# KMO_IO_MV1_2.net
KiCad netlist of a schematic drawn in EAGLE
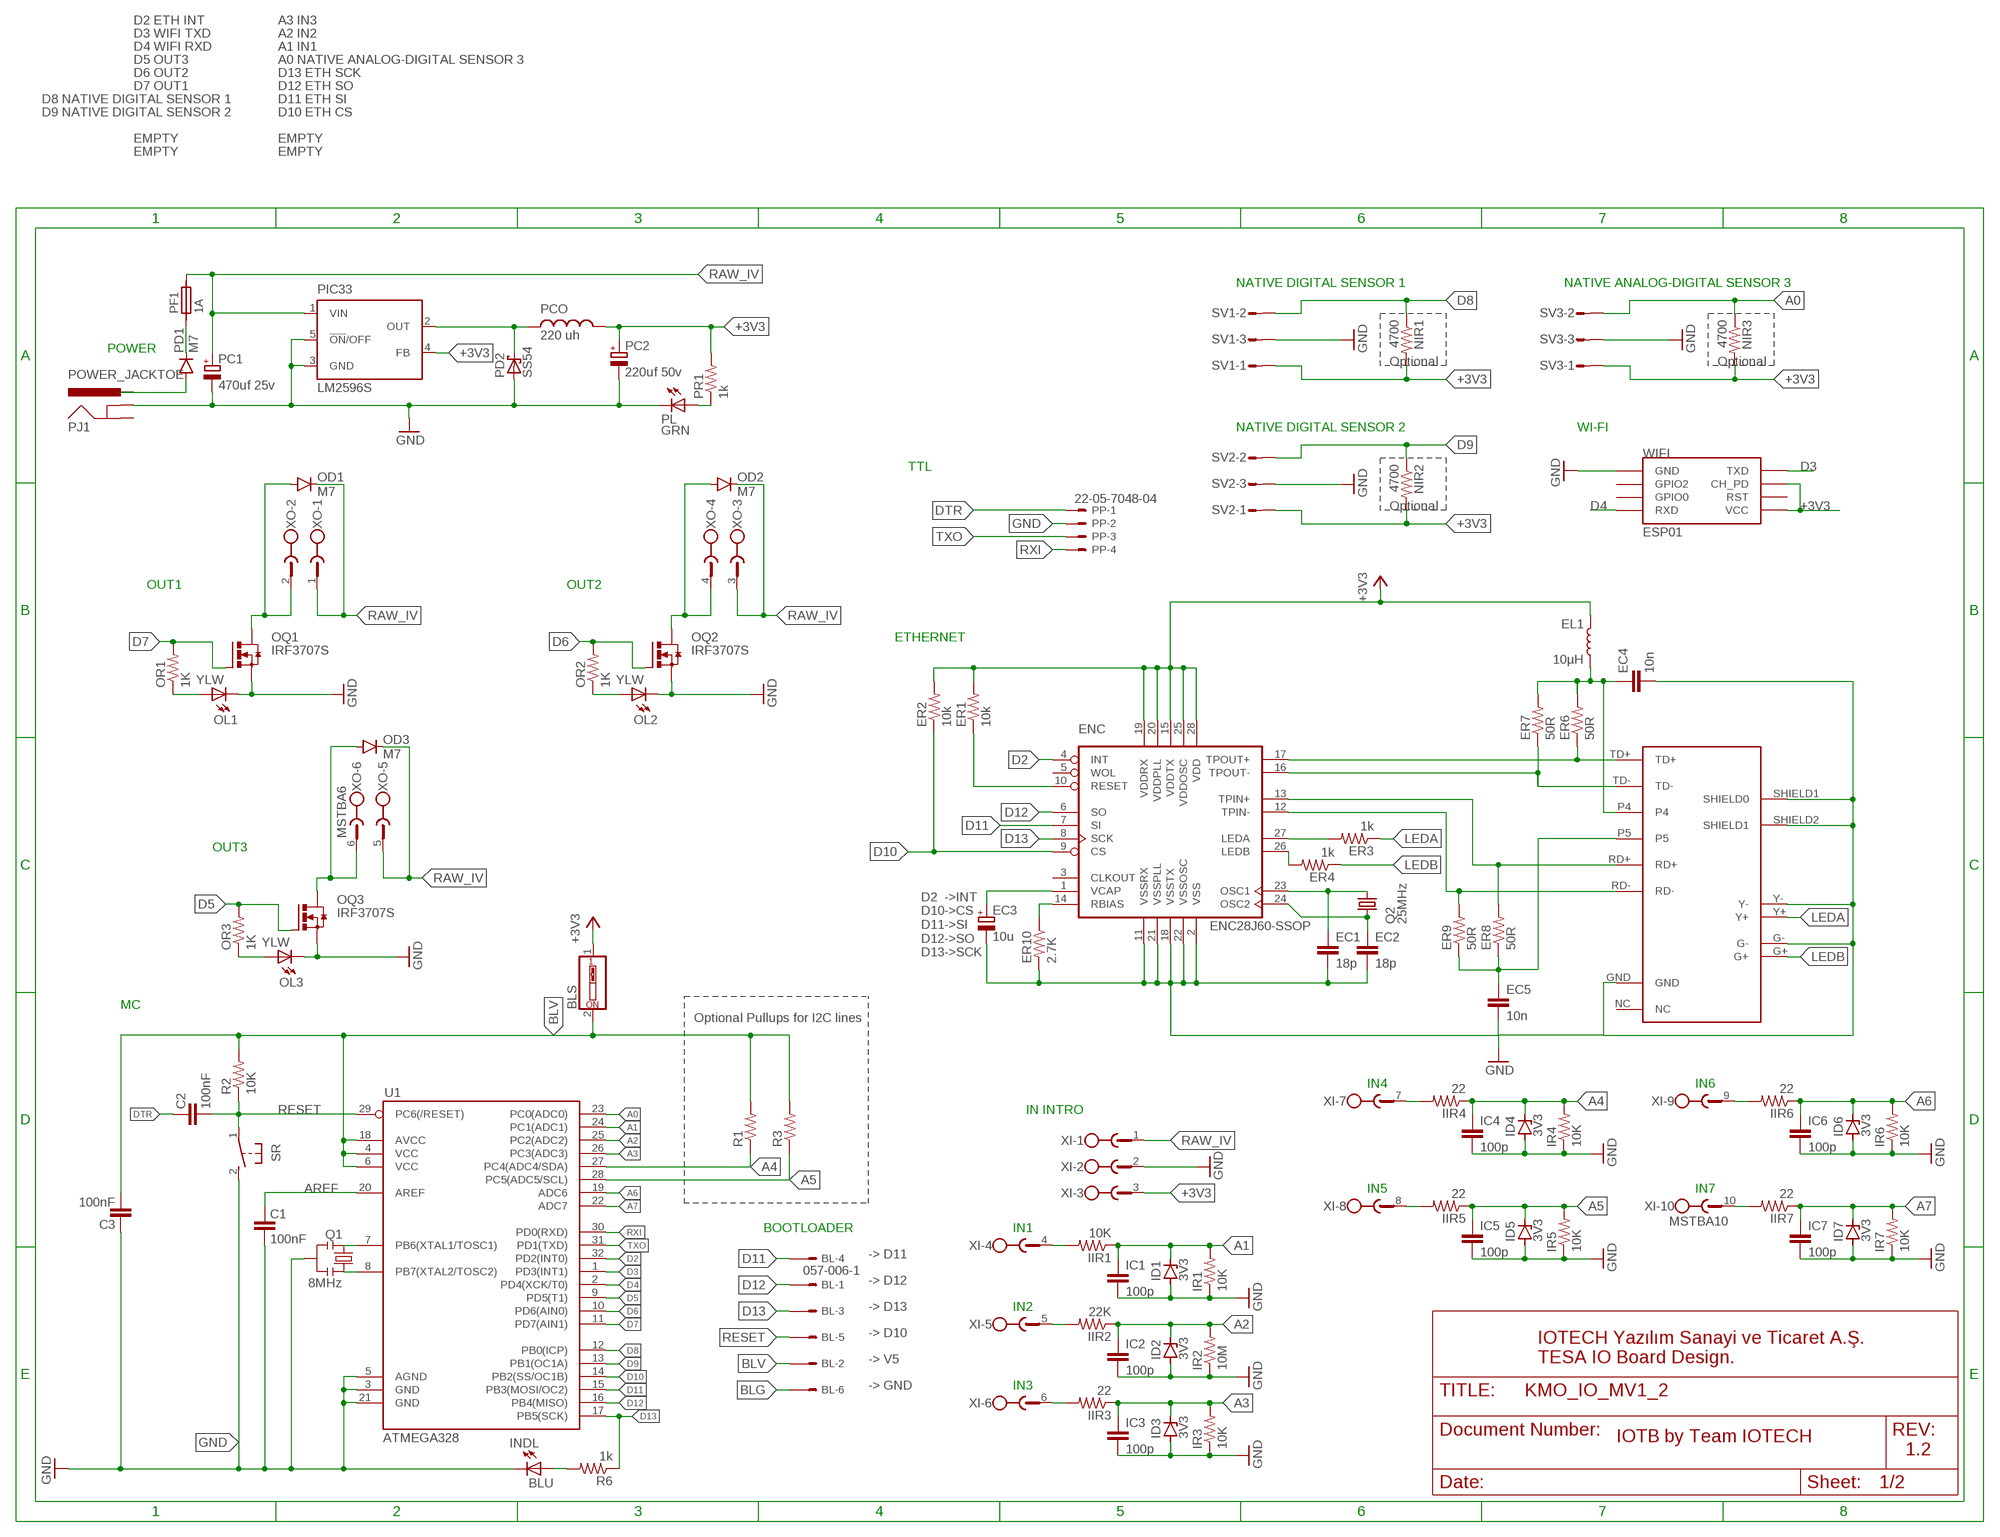
[diagram p0: schematic, sheet 1]
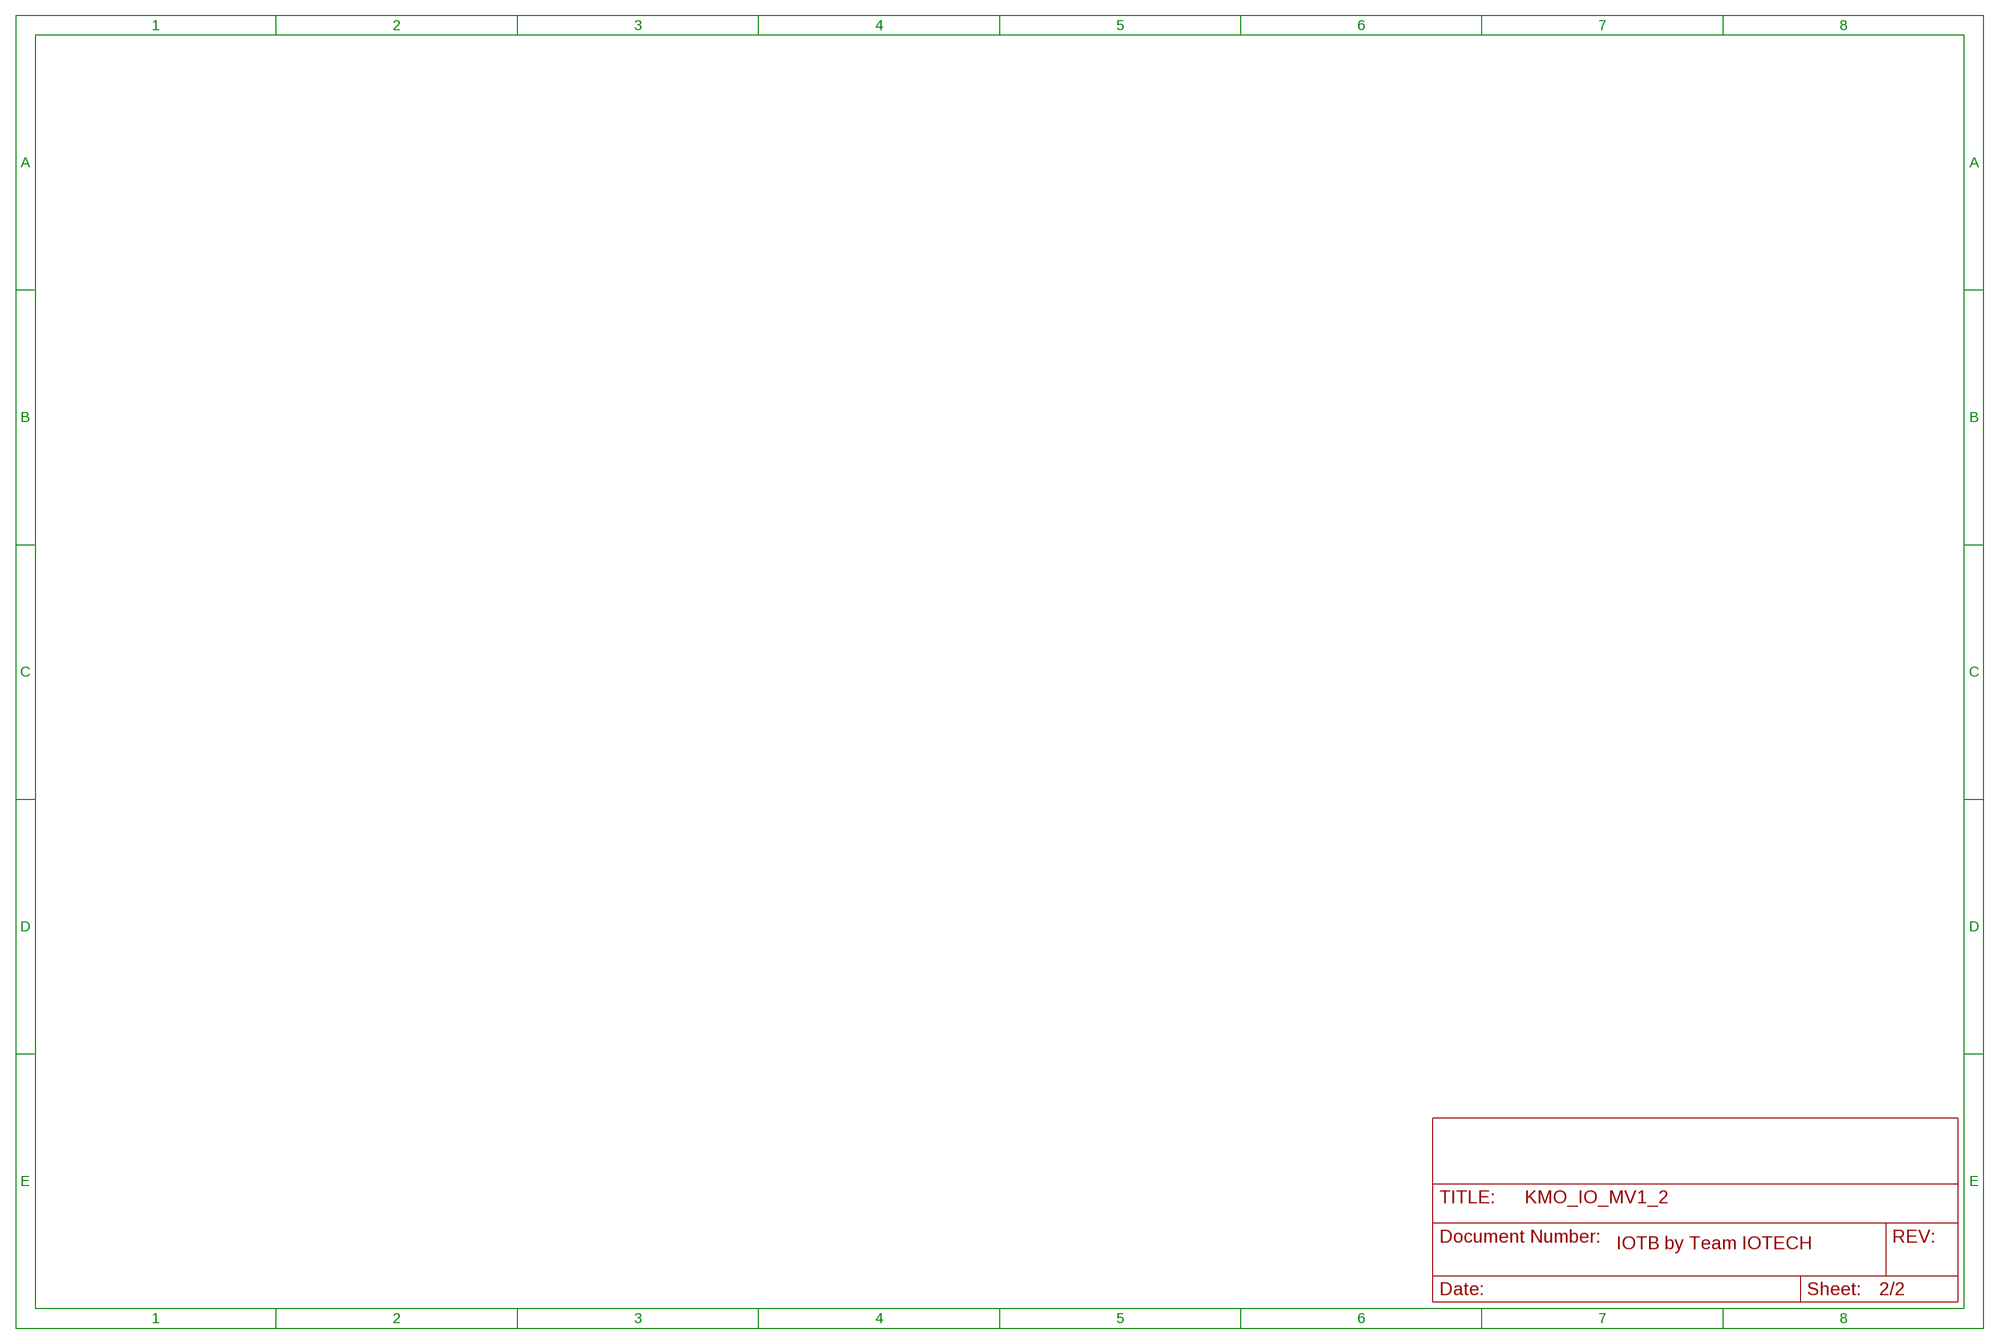
[diagram p1: schematic, sheet 2]

(export (version "E")
  (design (tool "Eeschema 10.0.6"))
  (components
    (comp (ref "BL")
      (value "057-006-1")
      (footprint "eagle-import:057-006-1")
      (libsource (lib "eagle-import") (part "057-006-1"))
    )
    (comp (ref "BLS")
      (value "SW_DIP-1")
      (footprint "eagle-import:EDG-01")
      (libsource (lib "eagle-import") (part "SW_DIP-1"))
    )
    (comp (ref "C1")
      (value "100nF")
      (footprint "eagle-import:0805")
      (libsource (lib "eagle-import") (part "CAP0805"))
    )
    (comp (ref "C2")
      (value "100nF")
      (footprint "eagle-import:0805")
      (libsource (lib "eagle-import") (part "CAP0805"))
    )
    (comp (ref "C3")
      (value "100nF")
      (footprint "eagle-import:0805")
      (libsource (lib "eagle-import") (part "CAP0805"))
    )
    (comp (ref "EC1")
      (value "18p")
      (footprint "eagle-import:0805")
      (libsource (lib "eagle-import") (part "CAP0805"))
    )
    (comp (ref "EC2")
      (value "18p")
      (footprint "eagle-import:0805")
      (libsource (lib "eagle-import") (part "CAP0805"))
    )
    (comp (ref "EC3")
      (value "10u")
      (footprint "eagle-import:CT3216")
      (libsource (lib "eagle-import") (part "CPOL-EUCT3216"))
    )
    (comp (ref "EC4")
      (value "10n")
      (footprint "eagle-import:0805")
      (libsource (lib "eagle-import") (part "CAP0805"))
    )
    (comp (ref "EC5")
      (value "10n")
      (footprint "eagle-import:0805")
      (libsource (lib "eagle-import") (part "CAP0805"))
    )
    (comp (ref "EL1")
      (value "10µH")
      (footprint "eagle-import:0805")
      (libsource (lib "eagle-import") (part "INDUCTOR-0805-3.3UH"))
    )
    (comp (ref "ENC")
      (value "ENC28J60-SSOP")
      (footprint "eagle-import:SSOP28")
      (libsource (lib "eagle-import") (part "ENC28J60-SSOP"))
    )
    (comp (ref "ER1")
      (value "10k")
      (footprint "eagle-import:0805")
      (libsource (lib "eagle-import") (part "RESISTOR0805-RES"))
    )
    (comp (ref "ER2")
      (value "10k")
      (footprint "eagle-import:0805")
      (libsource (lib "eagle-import") (part "RESISTOR0805-RES"))
    )
    (comp (ref "ER3")
      (value "1k")
      (footprint "eagle-import:0805")
      (libsource (lib "eagle-import") (part "RESISTOR0805-RES"))
    )
    (comp (ref "ER4")
      (value "1k")
      (footprint "eagle-import:0805")
      (libsource (lib "eagle-import") (part "RESISTOR0805-RES"))
    )
    (comp (ref "ER6")
      (value "50R")
      (footprint "eagle-import:0805")
      (libsource (lib "eagle-import") (part "RESISTOR0805-RES"))
    )
    (comp (ref "ER7")
      (value "50R")
      (footprint "eagle-import:0805")
      (libsource (lib "eagle-import") (part "RESISTOR0805-RES"))
    )
    (comp (ref "ER8")
      (value "50R")
      (footprint "eagle-import:0805")
      (libsource (lib "eagle-import") (part "RESISTOR0805-RES"))
    )
    (comp (ref "ER9")
      (value "50R")
      (footprint "eagle-import:0805")
      (libsource (lib "eagle-import") (part "RESISTOR0805-RES"))
    )
    (comp (ref "ER10")
      (value "2.7K")
      (footprint "eagle-import:0805")
      (libsource (lib "eagle-import") (part "RESISTOR0805-RES"))
    )
    (comp (ref "IC1")
      (value "100p")
      (footprint "eagle-import:0805")
      (libsource (lib "eagle-import") (part "CAP0805"))
    )
    (comp (ref "IC2")
      (value "100p")
      (footprint "eagle-import:0805")
      (libsource (lib "eagle-import") (part "CAP0805"))
    )
    (comp (ref "IC3")
      (value "100p")
      (footprint "eagle-import:0805")
      (libsource (lib "eagle-import") (part "CAP0805"))
    )
    (comp (ref "IC4")
      (value "100p")
      (footprint "eagle-import:0805")
      (libsource (lib "eagle-import") (part "CAP0805"))
    )
    (comp (ref "IC5")
      (value "100p")
      (footprint "eagle-import:0805")
      (libsource (lib "eagle-import") (part "CAP0805"))
    )
    (comp (ref "IC6")
      (value "100p")
      (footprint "eagle-import:0805")
      (libsource (lib "eagle-import") (part "CAP0805"))
    )
    (comp (ref "IC7")
      (value "100p")
      (footprint "eagle-import:0805")
      (libsource (lib "eagle-import") (part "CAP0805"))
    )
    (comp (ref "ID1")
      (value "3V3")
      (footprint "eagle-import:SOT23")
      (libsource (lib "eagle-import") (part "ZENER-DIODESOT23"))
    )
    (comp (ref "ID2")
      (value "3V3")
      (footprint "eagle-import:SOT23")
      (libsource (lib "eagle-import") (part "ZENER-DIODESOT23"))
    )
    (comp (ref "ID3")
      (value "3V3")
      (footprint "eagle-import:SOT23")
      (libsource (lib "eagle-import") (part "ZENER-DIODESOT23"))
    )
    (comp (ref "ID4")
      (value "3V3")
      (footprint "eagle-import:SOT23")
      (libsource (lib "eagle-import") (part "ZENER-DIODESOT23"))
    )
    (comp (ref "ID5")
      (value "3V3")
      (footprint "eagle-import:SOT23")
      (libsource (lib "eagle-import") (part "ZENER-DIODESOT23"))
    )
    (comp (ref "ID6")
      (value "3V3")
      (footprint "eagle-import:SOT23")
      (libsource (lib "eagle-import") (part "ZENER-DIODESOT23"))
    )
    (comp (ref "ID7")
      (value "3V3")
      (footprint "eagle-import:SOT23")
      (libsource (lib "eagle-import") (part "ZENER-DIODESOT23"))
    )
    (comp (ref "IIR1")
      (value "10K")
      (footprint "eagle-import:0805")
      (libsource (lib "eagle-import") (part "RESISTOR0805-RES"))
    )
    (comp (ref "IIR2")
      (value "22K")
      (footprint "eagle-import:0805")
      (libsource (lib "eagle-import") (part "RESISTOR0805-RES"))
    )
    (comp (ref "IIR3")
      (value "22")
      (footprint "eagle-import:0805")
      (libsource (lib "eagle-import") (part "RESISTOR0805-RES"))
    )
    (comp (ref "IIR4")
      (value "22")
      (footprint "eagle-import:0805")
      (libsource (lib "eagle-import") (part "RESISTOR0805-RES"))
    )
    (comp (ref "IIR5")
      (value "22")
      (footprint "eagle-import:0805")
      (libsource (lib "eagle-import") (part "RESISTOR0805-RES"))
    )
    (comp (ref "IIR6")
      (value "22")
      (footprint "eagle-import:0805")
      (libsource (lib "eagle-import") (part "RESISTOR0805-RES"))
    )
    (comp (ref "IIR7")
      (value "22")
      (footprint "eagle-import:0805")
      (libsource (lib "eagle-import") (part "RESISTOR0805-RES"))
    )
    (comp (ref "INDL")
      (value "BLU")
      (footprint "eagle-import:CHIP-LED0805")
      (libsource (lib "eagle-import") (part "LEDCHIP-LED0805"))
    )
    (comp (ref "IR1")
      (value "10K")
      (footprint "eagle-import:0805")
      (libsource (lib "eagle-import") (part "RESISTOR0805-RES"))
    )
    (comp (ref "IR2")
      (value "10M")
      (footprint "eagle-import:0805")
      (libsource (lib "eagle-import") (part "RESISTOR0805-RES"))
    )
    (comp (ref "IR3")
      (value "10K")
      (footprint "eagle-import:0805")
      (libsource (lib "eagle-import") (part "RESISTOR0805-RES"))
    )
    (comp (ref "IR4")
      (value "10K")
      (footprint "eagle-import:0805")
      (libsource (lib "eagle-import") (part "RESISTOR0805-RES"))
    )
    (comp (ref "IR5")
      (value "10K")
      (footprint "eagle-import:0805")
      (libsource (lib "eagle-import") (part "RESISTOR0805-RES"))
    )
    (comp (ref "IR6")
      (value "10K")
      (footprint "eagle-import:0805")
      (libsource (lib "eagle-import") (part "RESISTOR0805-RES"))
    )
    (comp (ref "IR7")
      (value "10K")
      (footprint "eagle-import:0805")
      (libsource (lib "eagle-import") (part "RESISTOR0805-RES"))
    )
    (comp (ref "NIR1")
      (value "4700")
      (footprint "eagle-import:0805")
      (libsource (lib "eagle-import") (part "RESISTOR0805-RES"))
    )
    (comp (ref "NIR2")
      (value "4700")
      (footprint "eagle-import:0805")
      (libsource (lib "eagle-import") (part "RESISTOR0805-RES"))
    )
    (comp (ref "NIR3")
      (value "4700")
      (footprint "eagle-import:0805")
      (libsource (lib "eagle-import") (part "RESISTOR0805-RES"))
    )
    (comp (ref "OD1")
      (value "M7")
      (footprint "eagle-import:SMA-DIODE")
      (libsource (lib "eagle-import") (part "DIODESMA"))
    )
    (comp (ref "OD2")
      (value "M7")
      (footprint "eagle-import:SMA-DIODE")
      (libsource (lib "eagle-import") (part "DIODESMA"))
    )
    (comp (ref "OD3")
      (value "M7")
      (footprint "eagle-import:SMA-DIODE")
      (libsource (lib "eagle-import") (part "DIODESMA"))
    )
    (comp (ref "OL1")
      (value "YLW")
      (footprint "eagle-import:CHIP-LED0805")
      (libsource (lib "eagle-import") (part "LEDCHIP-LED0805"))
    )
    (comp (ref "OL2")
      (value "YLW")
      (footprint "eagle-import:CHIP-LED0805")
      (libsource (lib "eagle-import") (part "LEDCHIP-LED0805"))
    )
    (comp (ref "OL3")
      (value "YLW")
      (footprint "eagle-import:CHIP-LED0805")
      (libsource (lib "eagle-import") (part "LEDCHIP-LED0805"))
    )
    (comp (ref "OQ1")
      (value "IRF3707S")
      (footprint "eagle-import:D2PACK")
      (libsource (lib "eagle-import") (part "IRF3704S"))
    )
    (comp (ref "OQ2")
      (value "IRF3707S")
      (footprint "eagle-import:D2PACK")
      (libsource (lib "eagle-import") (part "IRF3704S"))
    )
    (comp (ref "OQ3")
      (value "IRF3707S")
      (footprint "eagle-import:D2PACK")
      (libsource (lib "eagle-import") (part "IRF3704S"))
    )
    (comp (ref "OR1")
      (value "1K")
      (footprint "eagle-import:0805")
      (libsource (lib "eagle-import") (part "RESISTOR0805-RES"))
    )
    (comp (ref "OR2")
      (value "1K")
      (footprint "eagle-import:0805")
      (libsource (lib "eagle-import") (part "RESISTOR0805-RES"))
    )
    (comp (ref "OR3")
      (value "1K")
      (footprint "eagle-import:0805")
      (libsource (lib "eagle-import") (part "RESISTOR0805-RES"))
    )
    (comp (ref "PC1")
      (value "470uf 25v")
      (footprint "eagle-import:140CLH-1010")
      (libsource (lib "eagle-import") (part "CPOL-EU140CLH-1010"))
    )
    (comp (ref "PC2")
      (value "220uf 50v")
      (footprint "eagle-import:140CLH-1010")
      (libsource (lib "eagle-import") (part "CPOL-EU140CLH-1010"))
    )
    (comp (ref "PCO")
      (value "220 uh")
      (footprint "eagle-import:MSS1260")
      (libsource (lib "eagle-import") (part "MSS1260"))
    )
    (comp (ref "PD1")
      (value "M7")
      (footprint "eagle-import:SMA-DIODE")
      (libsource (lib "eagle-import") (part "DIODESMA"))
    )
    (comp (ref "PD2")
      (value "SS54")
      (footprint "eagle-import:SMB")
      (libsource (lib "eagle-import") (part "SCHOTTKY-DIODESMD"))
    )
    (comp (ref "PF1")
      (value "1A")
      (footprint "eagle-import:1820")
      (libsource (lib "eagle-import") (part "SIBA194600"))
    )
    (comp (ref "PIC33")
      (value "LM2596S")
      (footprint "eagle-import:TO263-5")
      (fields (field (name "MF") "NATIONAL SEMICONDUCTOR") (field (name "MPN") "LM2596S-ADJ/NOPB"))
      (libsource (lib "eagle-import") (part "LM2596S"))
    )
    (comp (ref "PJ1")
      (value "POWER_JACKTOE")
      (footprint "eagle-import:POWER_JACK_SMD_OVERPASTE_TOE")
      (libsource (lib "eagle-import") (part "POWER_JACKTOE"))
    )
    (comp (ref "PL")
      (value "GRN")
      (footprint "eagle-import:CHIP-LED0805")
      (libsource (lib "eagle-import") (part "LEDCHIP-LED0805"))
    )
    (comp (ref "PP")
      (value "22-05-7048-04")
      (footprint "eagle-import:7395-04")
      (fields (field (name "MF") "MOLEX"))
      (libsource (lib "eagle-import") (part "22-?-0405-7048"))
    )
    (comp (ref "PR1")
      (value "1k")
      (footprint "eagle-import:0805")
      (libsource (lib "eagle-import") (part "RESISTOR0805-RES"))
    )
    (comp (ref "Q1")
      (value "8MHz")
      (footprint "eagle-import:RESONATOR-SMD-1_1")
      (libsource (lib "eagle-import") (part "RESONATOR1{colon}1"))
    )
    (comp (ref "Q2")
      (value "25MHz")
      (footprint "eagle-import:5.0X3.2_2")
      (libsource (lib "eagle-import") (part "KX-9B"))
    )
    (comp (ref "R1")
      (value "RESISTOR0805-RES")
      (footprint "eagle-import:0805")
      (libsource (lib "eagle-import") (part "RESISTOR0805-RES"))
    )
    (comp (ref "R2")
      (value "10K")
      (footprint "eagle-import:0805")
      (libsource (lib "eagle-import") (part "RESISTOR0805-RES"))
    )
    (comp (ref "R3")
      (value "RESISTOR0805-RES")
      (footprint "eagle-import:0805")
      (libsource (lib "eagle-import") (part "RESISTOR0805-RES"))
    )
    (comp (ref "R6")
      (value "1k")
      (footprint "eagle-import:0805")
      (libsource (lib "eagle-import") (part "RESISTOR0805-RES"))
    )
    (comp (ref "SR")
      (value "31-XX")
      (footprint "eagle-import:B3F-31XX")
      (fields (field (name "MPN") "B3F-3100"))
      (libsource (lib "eagle-import") (part "31-XX"))
    )
    (comp (ref "SV1")
      (value "S03P")
      (footprint "eagle-import:S03P")
      (libsource (lib "eagle-import") (part "S03P"))
    )
    (comp (ref "SV2")
      (value "S03P")
      (footprint "eagle-import:S03P")
      (libsource (lib "eagle-import") (part "S03P"))
    )
    (comp (ref "SV3")
      (value "S03P")
      (footprint "eagle-import:S03P")
      (libsource (lib "eagle-import") (part "S03P"))
    )
    (comp (ref "U$2")
      (value "HR911105A")
      (footprint "eagle-import:RJ45")
      (libsource (lib "eagle-import") (part "HR911105A"))
    )
    (comp (ref "U1")
      (value "ATMEGA328")
      (footprint "eagle-import:TQFP32-08")
      (libsource (lib "eagle-import") (part "ATMEGA168"))
    )
    (comp (ref "WIFI")
      (value "ESP01")
      (footprint "eagle-import:ESP01")
      (libsource (lib "eagle-import") (part "ESP01"))
    )
    (comp (ref "XI")
      (value "MSTBA10")
      (footprint "eagle-import:MSTBA10")
      (fields (field (name "MF") "FARNELL") (field (name "MPN") "1757323"))
      (libsource (lib "eagle-import") (part "MSTBA10"))
    )
    (comp (ref "XO")
      (value "MSTBA6")
      (footprint "eagle-import:MSTBA6")
      (fields (field (name "MF") "FARNELL") (field (name "MPN") "1757284"))
      (libsource (lib "eagle-import") (part "MSTBA6"))
    )
  )
  (nets
    (net (code "1") (name "+3V3") (class "Default")
      (node (ref "BLS") (pin "1") (pinfunction "1_1") (pintype "passive"))
      (node (ref "EL1") (pin "1") (pinfunction "1_1") (pintype "passive"))
      (node (ref "ENC") (pin "15") (pinfunction "VDDTX_15") (pintype "power_in"))
      (node (ref "ENC") (pin "19") (pinfunction "VDDRX_19") (pintype "power_in"))
      (node (ref "ENC") (pin "20") (pinfunction "VDDPLL_20") (pintype "power_in"))
      (node (ref "ENC") (pin "25") (pinfunction "VDDOSC_25") (pintype "power_in"))
      (node (ref "ENC") (pin "28") (pinfunction "VDD_28") (pintype "power_in"))
      (node (ref "ER1") (pin "2") (pinfunction "2_2") (pintype "passive"))
      (node (ref "ER2") (pin "2") (pinfunction "2_2") (pintype "passive"))
      (node (ref "NIR1") (pin "2") (pinfunction "2_2") (pintype "passive"))
      (node (ref "NIR2") (pin "2") (pinfunction "2_2") (pintype "passive"))
      (node (ref "NIR3") (pin "2") (pinfunction "2_2") (pintype "passive"))
      (node (ref "PC2") (pin "+") (pinfunction "+_+") (pintype "passive"))
      (node (ref "PCO") (pin "P$1") (pinfunction "P$1_P$1") (pintype "passive"))
      (node (ref "PIC33") (pin "4") (pinfunction "FB_4") (pintype "input"))
      (node (ref "PR1") (pin "2") (pinfunction "2_2") (pintype "passive"))
      (node (ref "SV1") (pin "1") (pinfunction "S_1") (pintype "passive"))
      (node (ref "SV2") (pin "1") (pinfunction "S_1") (pintype "passive"))
      (node (ref "SV3") (pin "1") (pinfunction "S_1") (pintype "passive"))
      (node (ref "WIFI") (pin "CH_PD") (pinfunction "CH_PD_CH_PD") (pintype "bidirectional"))
      (node (ref "WIFI") (pin "VCC") (pinfunction "VCC_VCC") (pintype "bidirectional"))
      (node (ref "XI") (pin "3") (pinfunction "1_3") (pintype "passive"))
    )
    (net (code "2") (name "A0") (class "Default")
      (node (ref "NIR3") (pin "1") (pinfunction "1_1") (pintype "passive"))
      (node (ref "SV3") (pin "2") (pinfunction "S_2") (pintype "passive"))
      (node (ref "U1") (pin "23") (pinfunction "PC0(ADC0)_23") (pintype "bidirectional"))
    )
    (net (code "3") (name "A1") (class "Default")
      (node (ref "IC1") (pin "1") (pinfunction "1_1") (pintype "passive"))
      (node (ref "ID1") (pin "3") (pinfunction "C_3") (pintype "passive"))
      (node (ref "IIR1") (pin "1") (pinfunction "1_1") (pintype "passive"))
      (node (ref "IR1") (pin "2") (pinfunction "2_2") (pintype "passive"))
      (node (ref "U1") (pin "24") (pinfunction "PC1(ADC1)_24") (pintype "bidirectional"))
    )
    (net (code "4") (name "A2") (class "Default")
      (node (ref "IC2") (pin "1") (pinfunction "1_1") (pintype "passive"))
      (node (ref "ID2") (pin "3") (pinfunction "C_3") (pintype "passive"))
      (node (ref "IIR2") (pin "1") (pinfunction "1_1") (pintype "passive"))
      (node (ref "IR2") (pin "2") (pinfunction "2_2") (pintype "passive"))
      (node (ref "U1") (pin "25") (pinfunction "PC2(ADC2)_25") (pintype "bidirectional"))
    )
    (net (code "5") (name "A3") (class "Default")
      (node (ref "IC3") (pin "1") (pinfunction "1_1") (pintype "passive"))
      (node (ref "ID3") (pin "3") (pinfunction "C_3") (pintype "passive"))
      (node (ref "IIR3") (pin "1") (pinfunction "1_1") (pintype "passive"))
      (node (ref "IR3") (pin "2") (pinfunction "2_2") (pintype "passive"))
      (node (ref "U1") (pin "26") (pinfunction "PC3(ADC3)_26") (pintype "bidirectional"))
    )
    (net (code "6") (name "A4") (class "Default")
      (node (ref "IC4") (pin "1") (pinfunction "1_1") (pintype "passive"))
      (node (ref "ID4") (pin "3") (pinfunction "C_3") (pintype "passive"))
      (node (ref "IIR4") (pin "1") (pinfunction "1_1") (pintype "passive"))
      (node (ref "IR4") (pin "2") (pinfunction "2_2") (pintype "passive"))
      (node (ref "R1") (pin "1") (pinfunction "1_1") (pintype "passive"))
      (node (ref "U1") (pin "27") (pinfunction "PC4(ADC4/SDA)_27") (pintype "bidirectional"))
    )
    (net (code "7") (name "A5") (class "Default")
      (node (ref "IC5") (pin "1") (pinfunction "1_1") (pintype "passive"))
      (node (ref "ID5") (pin "3") (pinfunction "C_3") (pintype "passive"))
      (node (ref "IIR5") (pin "1") (pinfunction "1_1") (pintype "passive"))
      (node (ref "IR5") (pin "2") (pinfunction "2_2") (pintype "passive"))
      (node (ref "R3") (pin "1") (pinfunction "1_1") (pintype "passive"))
      (node (ref "U1") (pin "28") (pinfunction "PC5(ADC5/SCL)_28") (pintype "bidirectional"))
    )
    (net (code "8") (name "A6") (class "Default")
      (node (ref "IC6") (pin "1") (pinfunction "1_1") (pintype "passive"))
      (node (ref "ID6") (pin "3") (pinfunction "C_3") (pintype "passive"))
      (node (ref "IIR6") (pin "1") (pinfunction "1_1") (pintype "passive"))
      (node (ref "IR6") (pin "2") (pinfunction "2_2") (pintype "passive"))
      (node (ref "U1") (pin "19") (pinfunction "ADC6_19") (pintype "bidirectional"))
    )
    (net (code "9") (name "A7") (class "Default")
      (node (ref "IC7") (pin "1") (pinfunction "1_1") (pintype "passive"))
      (node (ref "ID7") (pin "3") (pinfunction "C_3") (pintype "passive"))
      (node (ref "IIR7") (pin "1") (pinfunction "1_1") (pintype "passive"))
      (node (ref "IR7") (pin "2") (pinfunction "2_2") (pintype "passive"))
      (node (ref "U1") (pin "22") (pinfunction "ADC7_22") (pintype "bidirectional"))
    )
    (net (code "10") (name "AREF") (class "Default")
      (node (ref "C1") (pin "2") (pinfunction "2_2") (pintype "passive"))
      (node (ref "U1") (pin "20") (pinfunction "AREF_20") (pintype "bidirectional"))
    )
    (net (code "11") (name "BLG") (class "Default")
      (node (ref "BL") (pin "6") (pinfunction "S_6") (pintype "passive"))
    )
    (net (code "12") (name "BLV") (class "Default")
      (node (ref "BL") (pin "2") (pinfunction "S_2") (pintype "passive"))
      (node (ref "BLS") (pin "2") (pinfunction "2_2") (pintype "passive"))
      (node (ref "C3") (pin "1") (pinfunction "1_1") (pintype "passive"))
      (node (ref "R1") (pin "2") (pinfunction "2_2") (pintype "passive"))
      (node (ref "R2") (pin "2") (pinfunction "2_2") (pintype "passive"))
      (node (ref "R3") (pin "2") (pinfunction "2_2") (pintype "passive"))
      (node (ref "U1") (pin "18") (pinfunction "AVCC_18") (pintype "bidirectional"))
      (node (ref "U1") (pin "4") (pinfunction "VCC_4") (pintype "bidirectional"))
      (node (ref "U1") (pin "6") (pinfunction "VCC_6") (pintype "bidirectional"))
    )
    (net (code "13") (name "D2") (class "Default")
      (node (ref "ENC") (pin "4") (pinfunction "INT_4") (pintype "output"))
      (node (ref "U1") (pin "32") (pinfunction "PD2(INT0)_32") (pintype "bidirectional"))
    )
    (net (code "14") (name "D3") (class "Default")
      (node (ref "U1") (pin "1") (pinfunction "PD3(INT1)_1") (pintype "bidirectional"))
      (node (ref "WIFI") (pin "TX") (pinfunction "TXD_TX") (pintype "bidirectional"))
    )
    (net (code "15") (name "D4") (class "Default")
      (node (ref "U1") (pin "2") (pinfunction "PD4(XCK/T0)_2") (pintype "bidirectional"))
      (node (ref "WIFI") (pin "RX") (pinfunction "RXD_RX") (pintype "bidirectional"))
    )
    (net (code "16") (name "D5") (class "Default")
      (node (ref "OQ3") (pin "1") (pinfunction "G_1") (pintype "passive"))
      (node (ref "OR3") (pin "2") (pinfunction "2_2") (pintype "passive"))
      (node (ref "U1") (pin "9") (pinfunction "PD5(T1)_9") (pintype "bidirectional"))
    )
    (net (code "17") (name "D6") (class "Default")
      (node (ref "OQ2") (pin "1") (pinfunction "G_1") (pintype "passive"))
      (node (ref "OR2") (pin "2") (pinfunction "2_2") (pintype "passive"))
      (node (ref "U1") (pin "10") (pinfunction "PD6(AIN0)_10") (pintype "bidirectional"))
    )
    (net (code "18") (name "D7") (class "Default")
      (node (ref "OQ1") (pin "1") (pinfunction "G_1") (pintype "passive"))
      (node (ref "OR1") (pin "2") (pinfunction "2_2") (pintype "passive"))
      (node (ref "U1") (pin "11") (pinfunction "PD7(AIN1)_11") (pintype "bidirectional"))
    )
    (net (code "19") (name "D8") (class "Default")
      (node (ref "NIR1") (pin "1") (pinfunction "1_1") (pintype "passive"))
      (node (ref "SV1") (pin "2") (pinfunction "S_2") (pintype "passive"))
      (node (ref "U1") (pin "12") (pinfunction "PB0(ICP)_12") (pintype "bidirectional"))
    )
    (net (code "20") (name "D9") (class "Default")
      (node (ref "NIR2") (pin "1") (pinfunction "1_1") (pintype "passive"))
      (node (ref "SV2") (pin "2") (pinfunction "S_2") (pintype "passive"))
      (node (ref "U1") (pin "13") (pinfunction "PB1(OC1A)_13") (pintype "bidirectional"))
    )
    (net (code "21") (name "D10") (class "Default")
      (node (ref "ENC") (pin "9") (pinfunction "CS_9") (pintype "input"))
      (node (ref "ER2") (pin "1") (pinfunction "1_1") (pintype "passive"))
      (node (ref "U1") (pin "14") (pinfunction "PB2(SS/OC1B)_14") (pintype "bidirectional"))
    )
    (net (code "22") (name "D11") (class "Default")
      (node (ref "BL") (pin "4") (pinfunction "S_4") (pintype "passive"))
      (node (ref "ENC") (pin "7") (pinfunction "SI_7") (pintype "input"))
      (node (ref "U1") (pin "15") (pinfunction "PB3(MOSI/OC2)_15") (pintype "bidirectional"))
    )
    (net (code "23") (name "D12") (class "Default")
      (node (ref "BL") (pin "1") (pinfunction "S_1") (pintype "passive"))
      (node (ref "ENC") (pin "6") (pinfunction "SO_6") (pintype "output"))
      (node (ref "U1") (pin "16") (pinfunction "PB4(MISO)_16") (pintype "bidirectional"))
    )
    (net (code "24") (name "D13") (class "Default")
      (node (ref "BL") (pin "3") (pinfunction "S_3") (pintype "passive"))
      (node (ref "ENC") (pin "8") (pinfunction "SCK_8") (pintype "input"))
      (node (ref "R6") (pin "1") (pinfunction "1_1") (pintype "passive"))
      (node (ref "U1") (pin "17") (pinfunction "PB5(SCK)_17") (pintype "bidirectional"))
    )
    (net (code "25") (name "DTR") (class "Default")
      (node (ref "C2") (pin "2") (pinfunction "2_2") (pintype "passive"))
      (node (ref "PP") (pin "1") (pinfunction "S_1") (pintype "passive"))
    )
    (net (code "26") (name "GND") (class "Default")
      (node (ref "C1") (pin "1") (pinfunction "1_1") (pintype "passive"))
      (node (ref "C3") (pin "2") (pinfunction "2_2") (pintype "passive"))
      (node (ref "EC1") (pin "2") (pinfunction "2_2") (pintype "passive"))
      (node (ref "EC2") (pin "2") (pinfunction "2_2") (pintype "passive"))
      (node (ref "EC3") (pin "-") (pinfunction "-_-") (pintype "passive"))
      (node (ref "EC4") (pin "2") (pinfunction "2_2") (pintype "passive"))
      (node (ref "EC5") (pin "2") (pinfunction "2_2") (pintype "passive"))
      (node (ref "ENC") (pin "11") (pinfunction "VSSRX_11") (pintype "power_in"))
      (node (ref "ENC") (pin "18") (pinfunction "VSSTX_18") (pintype "power_in"))
      (node (ref "ENC") (pin "2") (pinfunction "VSS_2") (pintype "power_in"))
      (node (ref "ENC") (pin "21") (pinfunction "VSSPLL_21") (pintype "power_in"))
      (node (ref "ENC") (pin "22") (pinfunction "VSSOSC_22") (pintype "power_in"))
      (node (ref "ER10") (pin "2") (pinfunction "2_2") (pintype "passive"))
      (node (ref "IC1") (pin "2") (pinfunction "2_2") (pintype "passive"))
      (node (ref "IC2") (pin "2") (pinfunction "2_2") (pintype "passive"))
      (node (ref "IC3") (pin "2") (pinfunction "2_2") (pintype "passive"))
      (node (ref "IC4") (pin "2") (pinfunction "2_2") (pintype "passive"))
      (node (ref "IC5") (pin "2") (pinfunction "2_2") (pintype "passive"))
      (node (ref "IC6") (pin "2") (pinfunction "2_2") (pintype "passive"))
      (node (ref "IC7") (pin "2") (pinfunction "2_2") (pintype "passive"))
      (node (ref "ID1") (pin "1") (pinfunction "A_1") (pintype "passive"))
      (node (ref "ID2") (pin "1") (pinfunction "A_1") (pintype "passive"))
      (node (ref "ID3") (pin "1") (pinfunction "A_1") (pintype "passive"))
      (node (ref "ID4") (pin "1") (pinfunction "A_1") (pintype "passive"))
      (node (ref "ID5") (pin "1") (pinfunction "A_1") (pintype "passive"))
      (node (ref "ID6") (pin "1") (pinfunction "A_1") (pintype "passive"))
      (node (ref "ID7") (pin "1") (pinfunction "A_1") (pintype "passive"))
      (node (ref "INDL") (pin "C") (pinfunction "C_C") (pintype "passive"))
      (node (ref "IR1") (pin "1") (pinfunction "1_1") (pintype "passive"))
      (node (ref "IR2") (pin "1") (pinfunction "1_1") (pintype "passive"))
      (node (ref "IR3") (pin "1") (pinfunction "1_1") (pintype "passive"))
      (node (ref "IR4") (pin "1") (pinfunction "1_1") (pintype "passive"))
      (node (ref "IR5") (pin "1") (pinfunction "1_1") (pintype "passive"))
      (node (ref "IR6") (pin "1") (pinfunction "1_1") (pintype "passive"))
      (node (ref "IR7") (pin "1") (pinfunction "1_1") (pintype "passive"))
      (node (ref "OL1") (pin "C") (pinfunction "C_C") (pintype "passive"))
      (node (ref "OL2") (pin "C") (pinfunction "C_C") (pintype "passive"))
      (node (ref "OL3") (pin "C") (pinfunction "C_C") (pintype "passive"))
      (node (ref "OQ1") (pin "3") (pinfunction "S_3") (pintype "passive"))
      (node (ref "OQ2") (pin "3") (pinfunction "S_3") (pintype "passive"))
      (node (ref "OQ3") (pin "3") (pinfunction "S_3") (pintype "passive"))
      (node (ref "PC1") (pin "-") (pinfunction "-_-") (pintype "passive"))
      (node (ref "PC2") (pin "-") (pinfunction "-_-") (pintype "passive"))
      (node (ref "PD2") (pin "A") (pinfunction "A_A") (pintype "passive"))
      (node (ref "PIC33") (pin "3") (pinfunction "GND_3") (pintype "power_in"))
      (node (ref "PIC33") (pin "5") (pinfunction "~{ON}/OFF_5") (pintype "input"))
      (node (ref "PJ1") (pin "GND") (pinfunction "GNDBREAK_GND") (pintype "bidirectional"))
      (node (ref "PL") (pin "C") (pinfunction "C_C") (pintype "passive"))
      (node (ref "PP") (pin "2") (pinfunction "S_2") (pintype "passive"))
      (node (ref "Q1") (pin "2") (pinfunction "2_2") (pintype "passive"))
      (node (ref "SR") (pin "2") (pinfunction "S_2") (pintype "passive"))
      (node (ref "SV1") (pin "3") (pinfunction "S_3") (pintype "passive"))
      (node (ref "SV2") (pin "3") (pinfunction "S_3") (pintype "passive"))
      (node (ref "SV3") (pin "3") (pinfunction "S_3") (pintype "passive"))
      (node (ref "U$2") (pin "G-") (pinfunction "G-_G-") (pintype "bidirectional"))
      (node (ref "U$2") (pin "GND") (pinfunction "GND_GND") (pintype "bidirectional"))
      (node (ref "U$2") (pin "SHIELD1") (pinfunction "SHIELD0_SHIELD1") (pintype "bidirectional"))
      (node (ref "U$2") (pin "SHIELD2") (pinfunction "SHIELD1_SHIELD2") (pintype "bidirectional"))
      (node (ref "U$2") (pin "Y-") (pinfunction "Y-_Y-") (pintype "bidirectional"))
      (node (ref "U1") (pin "21") (pinfunction "GND_21") (pintype "bidirectional"))
      (node (ref "U1") (pin "3") (pinfunction "GND_3") (pintype "bidirectional"))
      (node (ref "U1") (pin "5") (pinfunction "AGND_5") (pintype "bidirectional"))
      (node (ref "WIFI") (pin "GND") (pinfunction "GND_GND") (pintype "bidirectional"))
      (node (ref "XI") (pin "2") (pinfunction "1_2") (pintype "passive"))
    )
    (net (code "27") (name "LEDA") (class "Default")
      (node (ref "ER3") (pin "1") (pinfunction "1_1") (pintype "passive"))
      (node (ref "U$2") (pin "Y+") (pinfunction "Y+_Y+") (pintype "bidirectional"))
    )
    (net (code "28") (name "LEDB") (class "Default")
      (node (ref "ER4") (pin "1") (pinfunction "1_1") (pintype "passive"))
      (node (ref "U$2") (pin "G+") (pinfunction "G+_G+") (pintype "bidirectional"))
    )
    (net (code "29") (name "Net-(EC4-Pad1)") (class "Default")
      (node (ref "EC4") (pin "1") (pinfunction "1_1") (pintype "passive"))
      (node (ref "EL1") (pin "2") (pinfunction "2_2") (pintype "passive"))
      (node (ref "ER6") (pin "2") (pinfunction "2_2") (pintype "passive"))
      (node (ref "ER7") (pin "2") (pinfunction "2_2") (pintype "passive"))
      (node (ref "U$2") (pin "P4") (pinfunction "P4_P4") (pintype "bidirectional"))
    )
    (net (code "30") (name "Net-(EC5-Pad1)") (class "Default")
      (node (ref "EC5") (pin "1") (pinfunction "1_1") (pintype "passive"))
      (node (ref "ER8") (pin "1") (pinfunction "1_1") (pintype "passive"))
      (node (ref "ER9") (pin "1") (pinfunction "1_1") (pintype "passive"))
      (node (ref "U$2") (pin "P5") (pinfunction "P5_P5") (pintype "bidirectional"))
    )
    (net (code "31") (name "Net-(ENC-LEDA)") (class "Default")
      (node (ref "ENC") (pin "27") (pinfunction "LEDA_27") (pintype "output"))
      (node (ref "ER3") (pin "2") (pinfunction "2_2") (pintype "passive"))
    )
    (net (code "32") (name "Net-(ENC-LEDB)") (class "Default")
      (node (ref "ENC") (pin "26") (pinfunction "LEDB_26") (pintype "output"))
      (node (ref "ER4") (pin "2") (pinfunction "2_2") (pintype "passive"))
    )
    (net (code "33") (name "Net-(ENC-OSC1)") (class "Default")
      (node (ref "EC1") (pin "1") (pinfunction "1_1") (pintype "passive"))
      (node (ref "ENC") (pin "23") (pinfunction "OSC1_23") (pintype "input"))
      (node (ref "Q2") (pin "2") (pinfunction "2_2") (pintype "passive"))
    )
    (net (code "34") (name "Net-(ENC-OSC2)") (class "Default")
      (node (ref "EC2") (pin "1") (pinfunction "1_1") (pintype "passive"))
      (node (ref "ENC") (pin "24") (pinfunction "OSC2_24") (pintype "output"))
      (node (ref "Q2") (pin "1") (pinfunction "1_1") (pintype "passive"))
    )
    (net (code "35") (name "Net-(ENC-RBIAS)") (class "Default")
      (node (ref "ENC") (pin "14") (pinfunction "RBIAS_14") (pintype "passive"))
      (node (ref "ER10") (pin "1") (pinfunction "1_1") (pintype "passive"))
    )
    (net (code "36") (name "Net-(ENC-RESET)") (class "Default")
      (node (ref "ENC") (pin "10") (pinfunction "RESET_10") (pintype "input"))
      (node (ref "ER1") (pin "1") (pinfunction "1_1") (pintype "passive"))
    )
    (net (code "37") (name "Net-(ENC-TPIN+)") (class "Default")
      (node (ref "ENC") (pin "13") (pinfunction "TPIN+_13") (pintype "input"))
      (node (ref "ER8") (pin "2") (pinfunction "2_2") (pintype "passive"))
      (node (ref "U$2") (pin "RD+") (pinfunction "RD+_RD+") (pintype "bidirectional"))
    )
    (net (code "38") (name "Net-(ENC-TPIN-)") (class "Default")
      (node (ref "ENC") (pin "12") (pinfunction "TPIN-_12") (pintype "input"))
      (node (ref "ER9") (pin "2") (pinfunction "2_2") (pintype "passive"))
      (node (ref "U$2") (pin "RD-") (pinfunction "RD-_RD-") (pintype "bidirectional"))
    )
    (net (code "39") (name "Net-(ENC-TPOUT+)") (class "Default")
      (node (ref "ENC") (pin "17") (pinfunction "TPOUT+_17") (pintype "output"))
      (node (ref "ER6") (pin "1") (pinfunction "1_1") (pintype "passive"))
      (node (ref "U$2") (pin "TD+") (pinfunction "TD+_TD+") (pintype "bidirectional"))
    )
    (net (code "40") (name "Net-(ENC-TPOUT-)") (class "Default")
      (node (ref "ENC") (pin "16") (pinfunction "TPOUT-_16") (pintype "output"))
      (node (ref "ER7") (pin "1") (pinfunction "1_1") (pintype "passive"))
      (node (ref "U$2") (pin "TD-") (pinfunction "TD-_TD-") (pintype "bidirectional"))
    )
    (net (code "41") (name "Net-(ENC-VCAP)") (class "Default")
      (node (ref "EC3") (pin "+") (pinfunction "+_+") (pintype "passive"))
      (node (ref "ENC") (pin "1") (pinfunction "VCAP_1") (pintype "power_in"))
    )
    (net (code "42") (name "Net-(INDL-PadA)") (class "Default")
      (node (ref "INDL") (pin "A") (pinfunction "A_A") (pintype "passive"))
      (node (ref "R6") (pin "2") (pinfunction "2_2") (pintype "passive"))
    )
    (net (code "43") (name "Net-(OL1-PadA)") (class "Default")
      (node (ref "OL1") (pin "A") (pinfunction "A_A") (pintype "passive"))
      (node (ref "OR1") (pin "1") (pinfunction "1_1") (pintype "passive"))
    )
    (net (code "44") (name "Net-(OL2-PadA)") (class "Default")
      (node (ref "OL2") (pin "A") (pinfunction "A_A") (pintype "passive"))
      (node (ref "OR2") (pin "1") (pinfunction "1_1") (pintype "passive"))
    )
    (net (code "45") (name "Net-(OL3-PadA)") (class "Default")
      (node (ref "OL3") (pin "A") (pinfunction "A_A") (pintype "passive"))
      (node (ref "OR3") (pin "1") (pinfunction "1_1") (pintype "passive"))
    )
    (net (code "46") (name "Net-(OQ1-D)") (class "Default")
      (node (ref "OD1") (pin "A") (pinfunction "A_A") (pintype "passive"))
      (node (ref "OQ1") (pin "2") (pinfunction "D_2") (pintype "passive"))
      (node (ref "XO") (pin "2") (pinfunction "1_2") (pintype "passive"))
    )
    (net (code "47") (name "Net-(OQ2-D)") (class "Default")
      (node (ref "OD2") (pin "A") (pinfunction "A_A") (pintype "passive"))
      (node (ref "OQ2") (pin "2") (pinfunction "D_2") (pintype "passive"))
      (node (ref "XO") (pin "4") (pinfunction "1_4") (pintype "passive"))
    )
    (net (code "48") (name "Net-(OQ3-D)") (class "Default")
      (node (ref "OD3") (pin "A") (pinfunction "A_A") (pintype "passive"))
      (node (ref "OQ3") (pin "2") (pinfunction "D_2") (pintype "passive"))
      (node (ref "XO") (pin "6") (pinfunction "1_6") (pintype "passive"))
    )
    (net (code "49") (name "Net-(PD1-PadC)") (class "Default")
      (node (ref "PD1") (pin "C") (pinfunction "C_C") (pintype "passive"))
      (node (ref "PF1") (pin "1") (pinfunction "1_1") (pintype "passive"))
    )
    (net (code "50") (name "Net-(PIC33-OUT)") (class "Default")
      (node (ref "PCO") (pin "P$2") (pinfunction "P$2_P$2") (pintype "passive"))
      (node (ref "PD2") (pin "C") (pinfunction "C_C") (pintype "passive"))
      (node (ref "PIC33") (pin "2") (pinfunction "OUT_2") (pintype "output"))
    )
    (net (code "51") (name "Net-(PJ1-PWR)") (class "Default")
      (node (ref "PD1") (pin "A") (pinfunction "A_A") (pintype "passive"))
      (node (ref "PJ1") (pin "VIN0") (pinfunction "PWR_VIN0") (pintype "bidirectional"))
    )
    (net (code "52") (name "Net-(PL-PadA)") (class "Default")
      (node (ref "PL") (pin "A") (pinfunction "A_A") (pintype "passive"))
      (node (ref "PR1") (pin "1") (pinfunction "1_1") (pintype "passive"))
    )
    (net (code "53") (name "Net-(U1-PB6(XTAL1{slash}TOSC1))") (class "Default")
      (node (ref "Q1") (pin "1") (pinfunction "1_1") (pintype "passive"))
      (node (ref "U1") (pin "7") (pinfunction "PB6(XTAL1/TOSC1)_7") (pintype "bidirectional"))
    )
    (net (code "54") (name "Net-(U1-PB7(XTAL2{slash}TOSC2))") (class "Default")
      (node (ref "Q1") (pin "3") (pinfunction "3_3") (pintype "passive"))
      (node (ref "U1") (pin "8") (pinfunction "PB7(XTAL2/TOSC2)_8") (pintype "bidirectional"))
    )
    (net (code "55") (name "Net-(XIB-1)") (class "Default")
      (node (ref "IIR7") (pin "2") (pinfunction "2_2") (pintype "passive"))
      (node (ref "XI") (pin "10") (pinfunction "1_10") (pintype "passive"))
    )
    (net (code "56") (name "Net-(XIE-1)") (class "Default")
      (node (ref "IIR1") (pin "2") (pinfunction "2_2") (pintype "passive"))
      (node (ref "XI") (pin "4") (pinfunction "1_4") (pintype "passive"))
    )
    (net (code "57") (name "Net-(XIF-1)") (class "Default")
      (node (ref "IIR2") (pin "2") (pinfunction "2_2") (pintype "passive"))
      (node (ref "XI") (pin "5") (pinfunction "1_5") (pintype "passive"))
    )
    (net (code "58") (name "Net-(XIG-1)") (class "Default")
      (node (ref "IIR3") (pin "2") (pinfunction "2_2") (pintype "passive"))
      (node (ref "XI") (pin "6") (pinfunction "1_6") (pintype "passive"))
    )
    (net (code "59") (name "Net-(XIH-1)") (class "Default")
      (node (ref "IIR4") (pin "2") (pinfunction "2_2") (pintype "passive"))
      (node (ref "XI") (pin "7") (pinfunction "1_7") (pintype "passive"))
    )
    (net (code "60") (name "Net-(XII-1)") (class "Default")
      (node (ref "IIR5") (pin "2") (pinfunction "2_2") (pintype "passive"))
      (node (ref "XI") (pin "8") (pinfunction "1_8") (pintype "passive"))
    )
    (net (code "61") (name "Net-(XIJ-1)") (class "Default")
      (node (ref "IIR6") (pin "2") (pinfunction "2_2") (pintype "passive"))
      (node (ref "XI") (pin "9") (pinfunction "1_9") (pintype "passive"))
    )
    (net (code "62") (name "RAW_IV") (class "Default")
      (node (ref "OD1") (pin "C") (pinfunction "C_C") (pintype "passive"))
      (node (ref "OD2") (pin "C") (pinfunction "C_C") (pintype "passive"))
      (node (ref "OD3") (pin "C") (pinfunction "C_C") (pintype "passive"))
      (node (ref "PC1") (pin "+") (pinfunction "+_+") (pintype "passive"))
      (node (ref "PF1") (pin "2") (pinfunction "2_2") (pintype "passive"))
      (node (ref "PIC33") (pin "1") (pinfunction "VIN_1") (pintype "input"))
      (node (ref "XI") (pin "1") (pinfunction "1_1") (pintype "passive"))
      (node (ref "XO") (pin "1") (pinfunction "1_1") (pintype "passive"))
      (node (ref "XO") (pin "3") (pinfunction "1_3") (pintype "passive"))
      (node (ref "XO") (pin "5") (pinfunction "1_5") (pintype "passive"))
    )
    (net (code "63") (name "RESET") (class "Default")
      (node (ref "BL") (pin "5") (pinfunction "S_5") (pintype "passive"))
      (node (ref "C2") (pin "1") (pinfunction "1_1") (pintype "passive"))
      (node (ref "R2") (pin "1") (pinfunction "1_1") (pintype "passive"))
      (node (ref "SR") (pin "1") (pinfunction "P_1") (pintype "passive"))
      (node (ref "U1") (pin "29") (pinfunction "PC6(/RESET)_29") (pintype "bidirectional"))
    )
    (net (code "64") (name "RXI") (class "Default")
      (node (ref "PP") (pin "4") (pinfunction "S_4") (pintype "passive"))
      (node (ref "U1") (pin "30") (pinfunction "PD0(RXD)_30") (pintype "bidirectional"))
    )
    (net (code "65") (name "TXO") (class "Default")
      (node (ref "PP") (pin "3") (pinfunction "S_3") (pintype "passive"))
      (node (ref "U1") (pin "31") (pinfunction "PD1(TXD)_31") (pintype "bidirectional"))
    )
    (net (code "66") (name "unconnected-(ENC-CLKOUT-Pad3)") (class "Default")
      (node (ref "ENC") (pin "3") (pinfunction "CLKOUT_3") (pintype "output"))
    )
    (net (code "67") (name "unconnected-(ENC-WOL-Pad5)") (class "Default")
      (node (ref "ENC") (pin "5") (pinfunction "WOL_5") (pintype "output"))
    )
    (net (code "68") (name "unconnected-(PJ1-GND-PadP$4)") (class "Default")
      (node (ref "PJ1") (pin "P$4") (pinfunction "GND_P$4") (pintype "bidirectional"))
    )
    (net (code "69") (name "unconnected-(U$2-PadNC)") (class "Default")
      (node (ref "U$2") (pin "NC") (pinfunction "NC_NC") (pintype "bidirectional"))
    )
    (net (code "70") (name "unconnected-(WIFI-PadGPIO0)") (class "Default")
      (node (ref "WIFI") (pin "GPIO0") (pinfunction "GPIO0_GPIO0") (pintype "bidirectional"))
    )
    (net (code "71") (name "unconnected-(WIFI-PadGPIO2)") (class "Default")
      (node (ref "WIFI") (pin "GPIO2") (pinfunction "GPIO2_GPIO2") (pintype "bidirectional"))
    )
    (net (code "72") (name "unconnected-(WIFI-PadRST)") (class "Default")
      (node (ref "WIFI") (pin "RST") (pinfunction "RST_RST") (pintype "bidirectional"))
    )
  )
)
